# mb_01-3.net
KiCad netlist of a schematic drawn in EAGLE
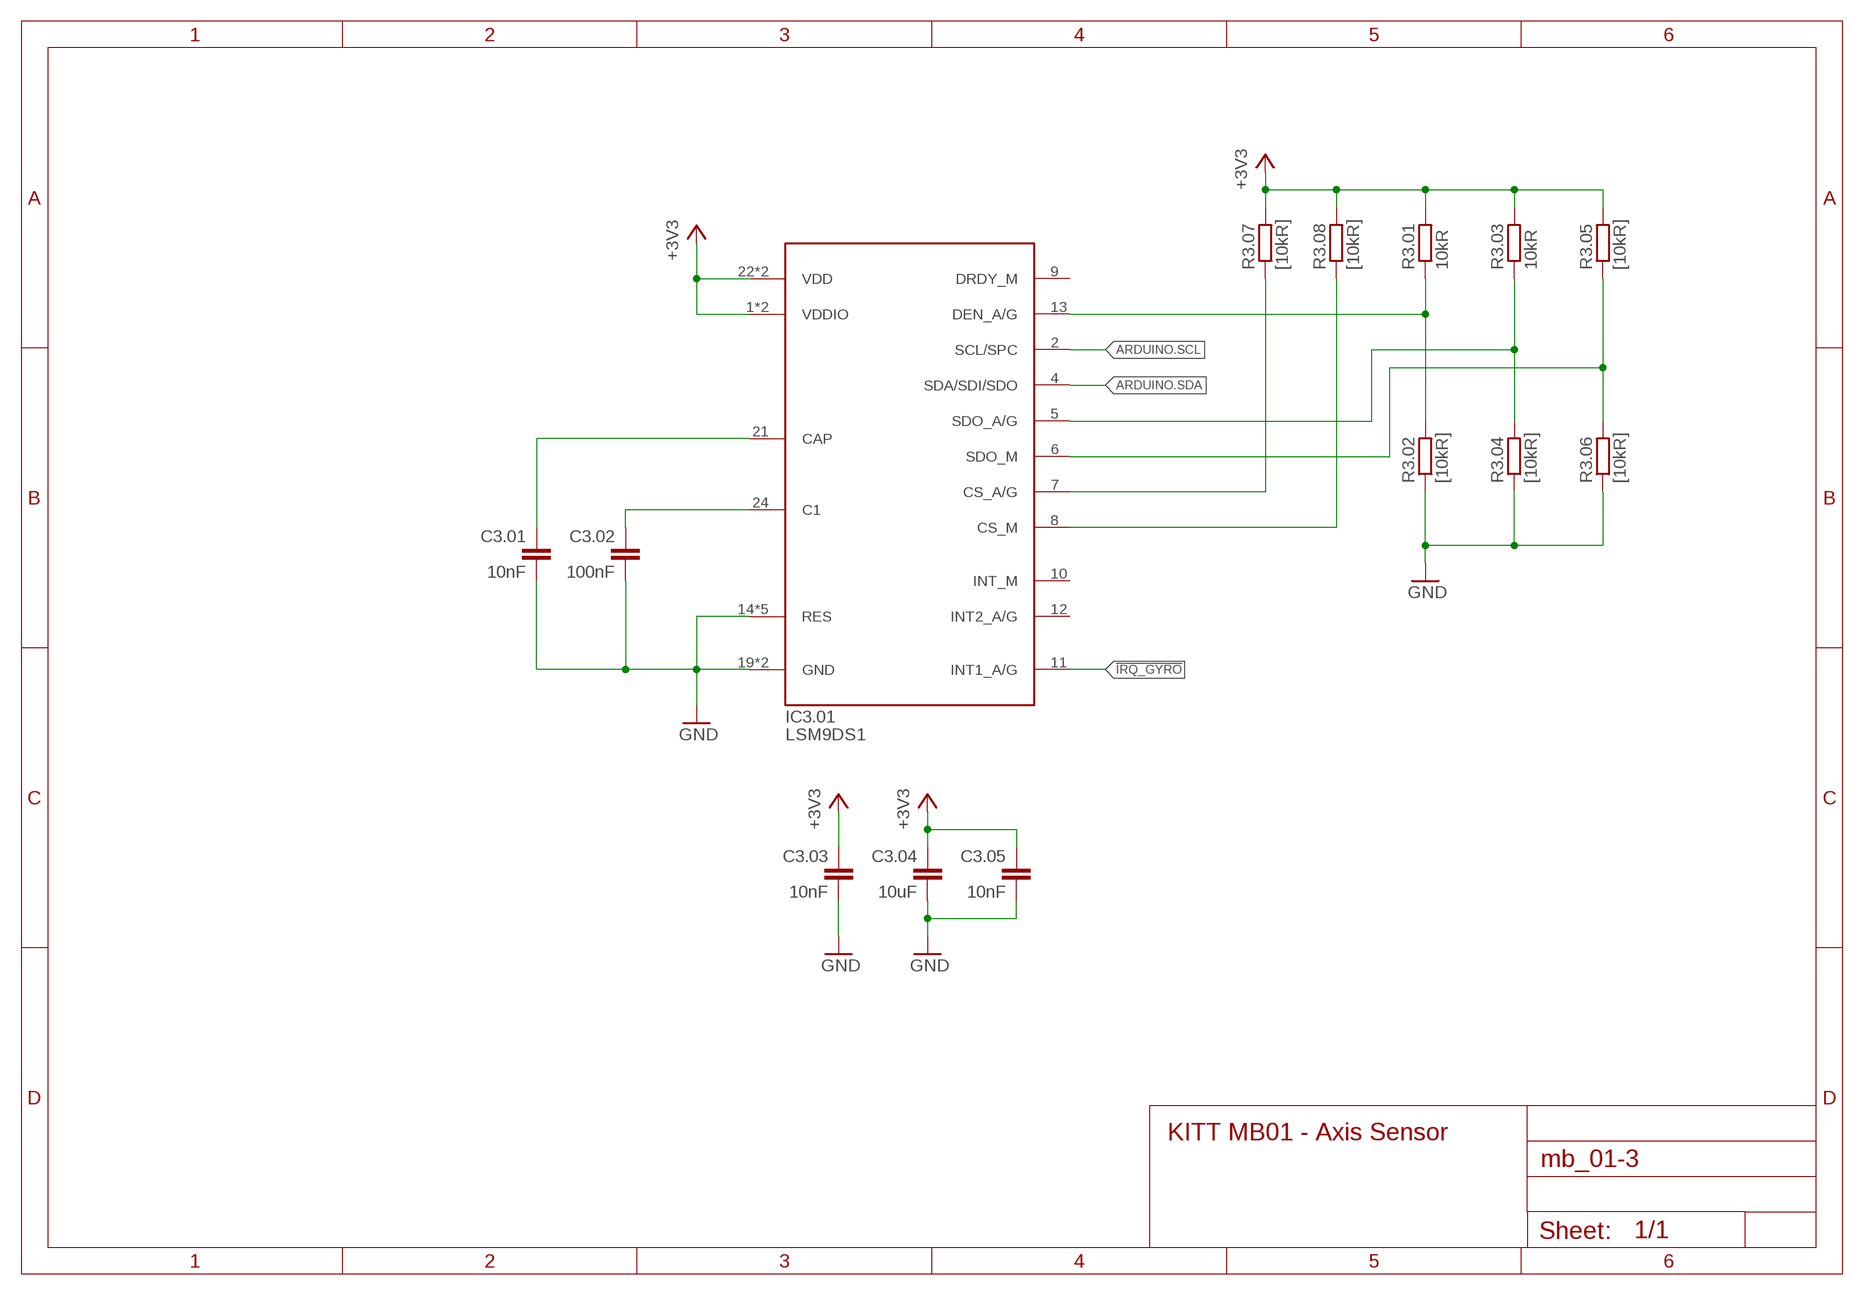
[diagram p0: schematic, sheet 1]

(export (version "E")
  (design (tool "Eeschema 10.0.6"))
  (components
    (comp (ref "C3.01")
      (value "10nF")
      (footprint "eagle-import:C0402")
      (libsource (lib "eagle-import") (part "C-EUC0402"))
    )
    (comp (ref "C3.02")
      (value "100nF")
      (footprint "eagle-import:C0402")
      (libsource (lib "eagle-import") (part "C-EUC0402"))
    )
    (comp (ref "C3.03")
      (value "10nF")
      (footprint "eagle-import:C0402")
      (libsource (lib "eagle-import") (part "C-EUC0402"))
    )
    (comp (ref "C3.04")
      (value "10uF")
      (footprint "eagle-import:C0603K")
      (libsource (lib "eagle-import") (part "C-EUC0603K"))
    )
    (comp (ref "C3.05")
      (value "10nF")
      (footprint "eagle-import:C0402")
      (libsource (lib "eagle-import") (part "C-EUC0402"))
    )
    (comp (ref "IC3.01")
      (value "LSM9DS1")
      (footprint "eagle-import:LGA-24")
      (fields (field (name "MF") "STMicroelectronics"))
      (libsource (lib "eagle-import") (part "LSM9DS1"))
    )
    (comp (ref "R3.01")
      (value "10kR")
      (footprint "eagle-import:R0402")
      (libsource (lib "eagle-import") (part "R-EU_R0402"))
    )
    (comp (ref "R3.02")
      (value "[10kR]")
      (footprint "eagle-import:R0402")
      (libsource (lib "eagle-import") (part "R-EU_R0402"))
    )
    (comp (ref "R3.03")
      (value "10kR")
      (footprint "eagle-import:R0402")
      (libsource (lib "eagle-import") (part "R-EU_R0402"))
    )
    (comp (ref "R3.04")
      (value "[10kR]")
      (footprint "eagle-import:R0402")
      (libsource (lib "eagle-import") (part "R-EU_R0402"))
    )
    (comp (ref "R3.05")
      (value "[10kR]")
      (footprint "eagle-import:R0402")
      (libsource (lib "eagle-import") (part "R-EU_R0402"))
    )
    (comp (ref "R3.06")
      (value "[10kR]")
      (footprint "eagle-import:R0402")
      (libsource (lib "eagle-import") (part "R-EU_R0402"))
    )
    (comp (ref "R3.07")
      (value "[10kR]")
      (footprint "eagle-import:R0402")
      (libsource (lib "eagle-import") (part "R-EU_R0402"))
    )
    (comp (ref "R3.08")
      (value "[10kR]")
      (footprint "eagle-import:R0402")
      (libsource (lib "eagle-import") (part "R-EU_R0402"))
    )
  )
  (nets
    (net (code "1") (name "+3V3") (class "Default")
      (node (ref "C3.03") (pin "1") (pinfunction "1_1") (pintype "passive"))
      (node (ref "C3.04") (pin "1") (pinfunction "1_1") (pintype "passive"))
      (node (ref "C3.05") (pin "1") (pinfunction "1_1") (pintype "passive"))
      (node (ref "IC3.01") (pin "1") (pinfunction "VDDIO_1") (pintype "bidirectional"))
      (node (ref "IC3.01") (pin "22") (pinfunction "VDD_22") (pintype "bidirectional"))
      (node (ref "IC3.01") (pin "23") (pinfunction "VDD_23") (pintype "bidirectional"))
      (node (ref "IC3.01") (pin "3") (pinfunction "VDDIO_3") (pintype "bidirectional"))
      (node (ref "R3.01") (pin "2") (pinfunction "2_2") (pintype "passive"))
      (node (ref "R3.03") (pin "2") (pinfunction "2_2") (pintype "passive"))
      (node (ref "R3.05") (pin "2") (pinfunction "2_2") (pintype "passive"))
      (node (ref "R3.07") (pin "2") (pinfunction "2_2") (pintype "passive"))
      (node (ref "R3.08") (pin "2") (pinfunction "2_2") (pintype "passive"))
    )
    (net (code "2") (name "/~{IRQ_GYRO}") (class "Default")
      (node (ref "IC3.01") (pin "11") (pinfunction "INT1_A/G_11") (pintype "bidirectional"))
    )
    (net (code "3") (name "ARDUINO.SCL") (class "Default")
      (node (ref "IC3.01") (pin "2") (pinfunction "SCL/SPC_2") (pintype "bidirectional"))
    )
    (net (code "4") (name "ARDUINO.SDA") (class "Default")
      (node (ref "IC3.01") (pin "4") (pinfunction "SDA/SDI/SDO_4") (pintype "bidirectional"))
    )
    (net (code "5") (name "GND") (class "Default")
      (node (ref "C3.01") (pin "2") (pinfunction "2_2") (pintype "passive"))
      (node (ref "C3.02") (pin "2") (pinfunction "2_2") (pintype "passive"))
      (node (ref "C3.03") (pin "2") (pinfunction "2_2") (pintype "passive"))
      (node (ref "C3.04") (pin "2") (pinfunction "2_2") (pintype "passive"))
      (node (ref "C3.05") (pin "2") (pinfunction "2_2") (pintype "passive"))
      (node (ref "IC3.01") (pin "14") (pinfunction "RES_14") (pintype "bidirectional"))
      (node (ref "IC3.01") (pin "15") (pinfunction "RES_15") (pintype "bidirectional"))
      (node (ref "IC3.01") (pin "16") (pinfunction "RES_16") (pintype "bidirectional"))
      (node (ref "IC3.01") (pin "17") (pinfunction "RES_17") (pintype "bidirectional"))
      (node (ref "IC3.01") (pin "18") (pinfunction "RES_18") (pintype "bidirectional"))
      (node (ref "IC3.01") (pin "19") (pinfunction "GND_19") (pintype "bidirectional"))
      (node (ref "IC3.01") (pin "20") (pinfunction "GND_20") (pintype "bidirectional"))
      (node (ref "R3.02") (pin "1") (pinfunction "1_1") (pintype "passive"))
      (node (ref "R3.04") (pin "1") (pinfunction "1_1") (pintype "passive"))
      (node (ref "R3.06") (pin "1") (pinfunction "1_1") (pintype "passive"))
    )
    (net (code "6") (name "Net-(IC3.01-C1)") (class "Default")
      (node (ref "C3.02") (pin "1") (pinfunction "1_1") (pintype "passive"))
      (node (ref "IC3.01") (pin "24") (pinfunction "C1_24") (pintype "bidirectional"))
    )
    (net (code "7") (name "Net-(IC3.01-CAP)") (class "Default")
      (node (ref "C3.01") (pin "1") (pinfunction "1_1") (pintype "passive"))
      (node (ref "IC3.01") (pin "21") (pinfunction "CAP_21") (pintype "bidirectional"))
    )
    (net (code "8") (name "Net-(IC3.01-CS_A{slash}G)") (class "Default")
      (node (ref "IC3.01") (pin "7") (pinfunction "CS_A/G_7") (pintype "bidirectional"))
      (node (ref "R3.07") (pin "1") (pinfunction "1_1") (pintype "passive"))
    )
    (net (code "9") (name "Net-(IC3.01-CS_M)") (class "Default")
      (node (ref "IC3.01") (pin "8") (pinfunction "CS_M_8") (pintype "bidirectional"))
      (node (ref "R3.08") (pin "1") (pinfunction "1_1") (pintype "passive"))
    )
    (net (code "10") (name "Net-(IC3.01-DEN_A{slash}G)") (class "Default")
      (node (ref "IC3.01") (pin "13") (pinfunction "DEN_A/G_13") (pintype "bidirectional"))
      (node (ref "R3.01") (pin "1") (pinfunction "1_1") (pintype "passive"))
      (node (ref "R3.02") (pin "2") (pinfunction "2_2") (pintype "passive"))
    )
    (net (code "11") (name "Net-(IC3.01-SDO_A{slash}G)") (class "Default")
      (node (ref "IC3.01") (pin "5") (pinfunction "SDO_A/G_5") (pintype "bidirectional"))
      (node (ref "R3.03") (pin "1") (pinfunction "1_1") (pintype "passive"))
      (node (ref "R3.04") (pin "2") (pinfunction "2_2") (pintype "passive"))
    )
    (net (code "12") (name "Net-(IC3.01-SDO_M)") (class "Default")
      (node (ref "IC3.01") (pin "6") (pinfunction "SDO_M_6") (pintype "bidirectional"))
      (node (ref "R3.05") (pin "1") (pinfunction "1_1") (pintype "passive"))
      (node (ref "R3.06") (pin "2") (pinfunction "2_2") (pintype "passive"))
    )
    (net (code "13") (name "unconnected-(IC3.01-DRDY_M-Pad9)") (class "Default")
      (node (ref "IC3.01") (pin "9") (pinfunction "DRDY_M_9") (pintype "bidirectional"))
    )
    (net (code "14") (name "unconnected-(IC3.01-INT2_A{slash}G-Pad12)") (class "Default")
      (node (ref "IC3.01") (pin "12") (pinfunction "INT2_A/G_12") (pintype "bidirectional"))
    )
    (net (code "15") (name "unconnected-(IC3.01-INT_M-Pad10)") (class "Default")
      (node (ref "IC3.01") (pin "10") (pinfunction "INT_M_10") (pintype "bidirectional"))
    )
  )
)
